# SOIC16_breakout.net
KiCad netlist of a schematic drawn in EAGLE
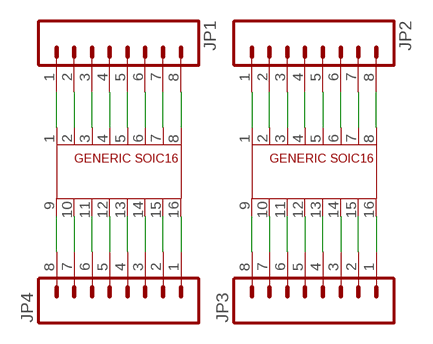
[diagram p0: schematic, sheet 1]

(export (version "E")
  (design (tool "Eeschema 10.0.6"))
  (components
    (comp (ref "JP1")
      (value "M08")
      (footprint "eagle-import:1X08")
      (libsource (lib "eagle-import") (part "M08"))
    )
    (comp (ref "JP2")
      (value "M08")
      (footprint "eagle-import:1X08")
      (libsource (lib "eagle-import") (part "M08"))
    )
    (comp (ref "JP3")
      (value "M08")
      (footprint "eagle-import:1X08")
      (libsource (lib "eagle-import") (part "M08"))
    )
    (comp (ref "JP4")
      (value "M08")
      (footprint "eagle-import:1X08")
      (libsource (lib "eagle-import") (part "M08"))
    )
    (comp (ref "U$1")
      (value "SOIC16")
      (footprint "eagle-import:SOIC-16")
      (libsource (lib "eagle-import") (part "SOIC16"))
    )
    (comp (ref "U$2")
      (value "SOIC16")
      (footprint "eagle-import:SOIC-16")
      (libsource (lib "eagle-import") (part "SOIC16"))
    )
  )
  (nets
    (net (code "1") (name "Net-(U$1-P$1)") (class "Default")
      (node (ref "JP1") (pin "1") (pinfunction "1_1") (pintype "passive"))
      (node (ref "U$1") (pin "1") (pinfunction "P$1_1") (pintype "bidirectional"))
    )
    (net (code "2") (name "Net-(U$1-P$2)") (class "Default")
      (node (ref "JP1") (pin "2") (pinfunction "2_2") (pintype "passive"))
      (node (ref "U$1") (pin "2") (pinfunction "P$2_2") (pintype "bidirectional"))
    )
    (net (code "3") (name "Net-(U$1-P$3)") (class "Default")
      (node (ref "JP1") (pin "3") (pinfunction "3_3") (pintype "passive"))
      (node (ref "U$1") (pin "3") (pinfunction "P$3_3") (pintype "bidirectional"))
    )
    (net (code "4") (name "Net-(U$1-P$4)") (class "Default")
      (node (ref "JP1") (pin "4") (pinfunction "4_4") (pintype "passive"))
      (node (ref "U$1") (pin "4") (pinfunction "P$4_4") (pintype "bidirectional"))
    )
    (net (code "5") (name "Net-(U$1-P$5)") (class "Default")
      (node (ref "JP1") (pin "5") (pinfunction "5_5") (pintype "passive"))
      (node (ref "U$1") (pin "5") (pinfunction "P$5_5") (pintype "bidirectional"))
    )
    (net (code "6") (name "Net-(U$1-P$6)") (class "Default")
      (node (ref "JP1") (pin "6") (pinfunction "6_6") (pintype "passive"))
      (node (ref "U$1") (pin "6") (pinfunction "P$6_6") (pintype "bidirectional"))
    )
    (net (code "7") (name "Net-(U$1-P$7)") (class "Default")
      (node (ref "JP1") (pin "7") (pinfunction "7_7") (pintype "passive"))
      (node (ref "U$1") (pin "7") (pinfunction "P$7_7") (pintype "bidirectional"))
    )
    (net (code "8") (name "Net-(U$1-P$8)") (class "Default")
      (node (ref "JP1") (pin "8") (pinfunction "8_8") (pintype "passive"))
      (node (ref "U$1") (pin "8") (pinfunction "P$8_8") (pintype "bidirectional"))
    )
    (net (code "9") (name "Net-(U$1-P$9)") (class "Default")
      (node (ref "JP4") (pin "8") (pinfunction "8_8") (pintype "passive"))
      (node (ref "U$1") (pin "9") (pinfunction "P$9_9") (pintype "bidirectional"))
    )
    (net (code "10") (name "Net-(U$1-P$10)") (class "Default")
      (node (ref "JP4") (pin "7") (pinfunction "7_7") (pintype "passive"))
      (node (ref "U$1") (pin "10") (pinfunction "P$10_10") (pintype "bidirectional"))
    )
    (net (code "11") (name "Net-(U$1-P$11)") (class "Default")
      (node (ref "JP4") (pin "6") (pinfunction "6_6") (pintype "passive"))
      (node (ref "U$1") (pin "11") (pinfunction "P$11_11") (pintype "bidirectional"))
    )
    (net (code "12") (name "Net-(U$1-P$12)") (class "Default")
      (node (ref "JP4") (pin "5") (pinfunction "5_5") (pintype "passive"))
      (node (ref "U$1") (pin "12") (pinfunction "P$12_12") (pintype "bidirectional"))
    )
    (net (code "13") (name "Net-(U$1-P$13)") (class "Default")
      (node (ref "JP4") (pin "4") (pinfunction "4_4") (pintype "passive"))
      (node (ref "U$1") (pin "13") (pinfunction "P$13_13") (pintype "bidirectional"))
    )
    (net (code "14") (name "Net-(U$1-P$14)") (class "Default")
      (node (ref "JP4") (pin "3") (pinfunction "3_3") (pintype "passive"))
      (node (ref "U$1") (pin "14") (pinfunction "P$14_14") (pintype "bidirectional"))
    )
    (net (code "15") (name "Net-(U$1-P$15)") (class "Default")
      (node (ref "JP4") (pin "2") (pinfunction "2_2") (pintype "passive"))
      (node (ref "U$1") (pin "15") (pinfunction "P$15_15") (pintype "bidirectional"))
    )
    (net (code "16") (name "Net-(U$1-P$16)") (class "Default")
      (node (ref "JP4") (pin "1") (pinfunction "1_1") (pintype "passive"))
      (node (ref "U$1") (pin "16") (pinfunction "P$16_16") (pintype "bidirectional"))
    )
    (net (code "17") (name "Net-(U$2-P$1)") (class "Default")
      (node (ref "JP2") (pin "1") (pinfunction "1_1") (pintype "passive"))
      (node (ref "U$2") (pin "1") (pinfunction "P$1_1") (pintype "bidirectional"))
    )
    (net (code "18") (name "Net-(U$2-P$2)") (class "Default")
      (node (ref "JP2") (pin "2") (pinfunction "2_2") (pintype "passive"))
      (node (ref "U$2") (pin "2") (pinfunction "P$2_2") (pintype "bidirectional"))
    )
    (net (code "19") (name "Net-(U$2-P$3)") (class "Default")
      (node (ref "JP2") (pin "3") (pinfunction "3_3") (pintype "passive"))
      (node (ref "U$2") (pin "3") (pinfunction "P$3_3") (pintype "bidirectional"))
    )
    (net (code "20") (name "Net-(U$2-P$4)") (class "Default")
      (node (ref "JP2") (pin "4") (pinfunction "4_4") (pintype "passive"))
      (node (ref "U$2") (pin "4") (pinfunction "P$4_4") (pintype "bidirectional"))
    )
    (net (code "21") (name "Net-(U$2-P$5)") (class "Default")
      (node (ref "JP2") (pin "5") (pinfunction "5_5") (pintype "passive"))
      (node (ref "U$2") (pin "5") (pinfunction "P$5_5") (pintype "bidirectional"))
    )
    (net (code "22") (name "Net-(U$2-P$6)") (class "Default")
      (node (ref "JP2") (pin "6") (pinfunction "6_6") (pintype "passive"))
      (node (ref "U$2") (pin "6") (pinfunction "P$6_6") (pintype "bidirectional"))
    )
    (net (code "23") (name "Net-(U$2-P$7)") (class "Default")
      (node (ref "JP2") (pin "7") (pinfunction "7_7") (pintype "passive"))
      (node (ref "U$2") (pin "7") (pinfunction "P$7_7") (pintype "bidirectional"))
    )
    (net (code "24") (name "Net-(U$2-P$8)") (class "Default")
      (node (ref "JP2") (pin "8") (pinfunction "8_8") (pintype "passive"))
      (node (ref "U$2") (pin "8") (pinfunction "P$8_8") (pintype "bidirectional"))
    )
    (net (code "25") (name "Net-(U$2-P$9)") (class "Default")
      (node (ref "JP3") (pin "8") (pinfunction "8_8") (pintype "passive"))
      (node (ref "U$2") (pin "9") (pinfunction "P$9_9") (pintype "bidirectional"))
    )
    (net (code "26") (name "Net-(U$2-P$10)") (class "Default")
      (node (ref "JP3") (pin "7") (pinfunction "7_7") (pintype "passive"))
      (node (ref "U$2") (pin "10") (pinfunction "P$10_10") (pintype "bidirectional"))
    )
    (net (code "27") (name "Net-(U$2-P$11)") (class "Default")
      (node (ref "JP3") (pin "6") (pinfunction "6_6") (pintype "passive"))
      (node (ref "U$2") (pin "11") (pinfunction "P$11_11") (pintype "bidirectional"))
    )
    (net (code "28") (name "Net-(U$2-P$12)") (class "Default")
      (node (ref "JP3") (pin "5") (pinfunction "5_5") (pintype "passive"))
      (node (ref "U$2") (pin "12") (pinfunction "P$12_12") (pintype "bidirectional"))
    )
    (net (code "29") (name "Net-(U$2-P$13)") (class "Default")
      (node (ref "JP3") (pin "4") (pinfunction "4_4") (pintype "passive"))
      (node (ref "U$2") (pin "13") (pinfunction "P$13_13") (pintype "bidirectional"))
    )
    (net (code "30") (name "Net-(U$2-P$14)") (class "Default")
      (node (ref "JP3") (pin "3") (pinfunction "3_3") (pintype "passive"))
      (node (ref "U$2") (pin "14") (pinfunction "P$14_14") (pintype "bidirectional"))
    )
    (net (code "31") (name "Net-(U$2-P$15)") (class "Default")
      (node (ref "JP3") (pin "2") (pinfunction "2_2") (pintype "passive"))
      (node (ref "U$2") (pin "15") (pinfunction "P$15_15") (pintype "bidirectional"))
    )
    (net (code "32") (name "Net-(U$2-P$16)") (class "Default")
      (node (ref "JP3") (pin "1") (pinfunction "1_1") (pintype "passive"))
      (node (ref "U$2") (pin "16") (pinfunction "P$16_16") (pintype "bidirectional"))
    )
  )
)
